# md_mini_smd.net
KiCad netlist of a schematic drawn in EAGLE
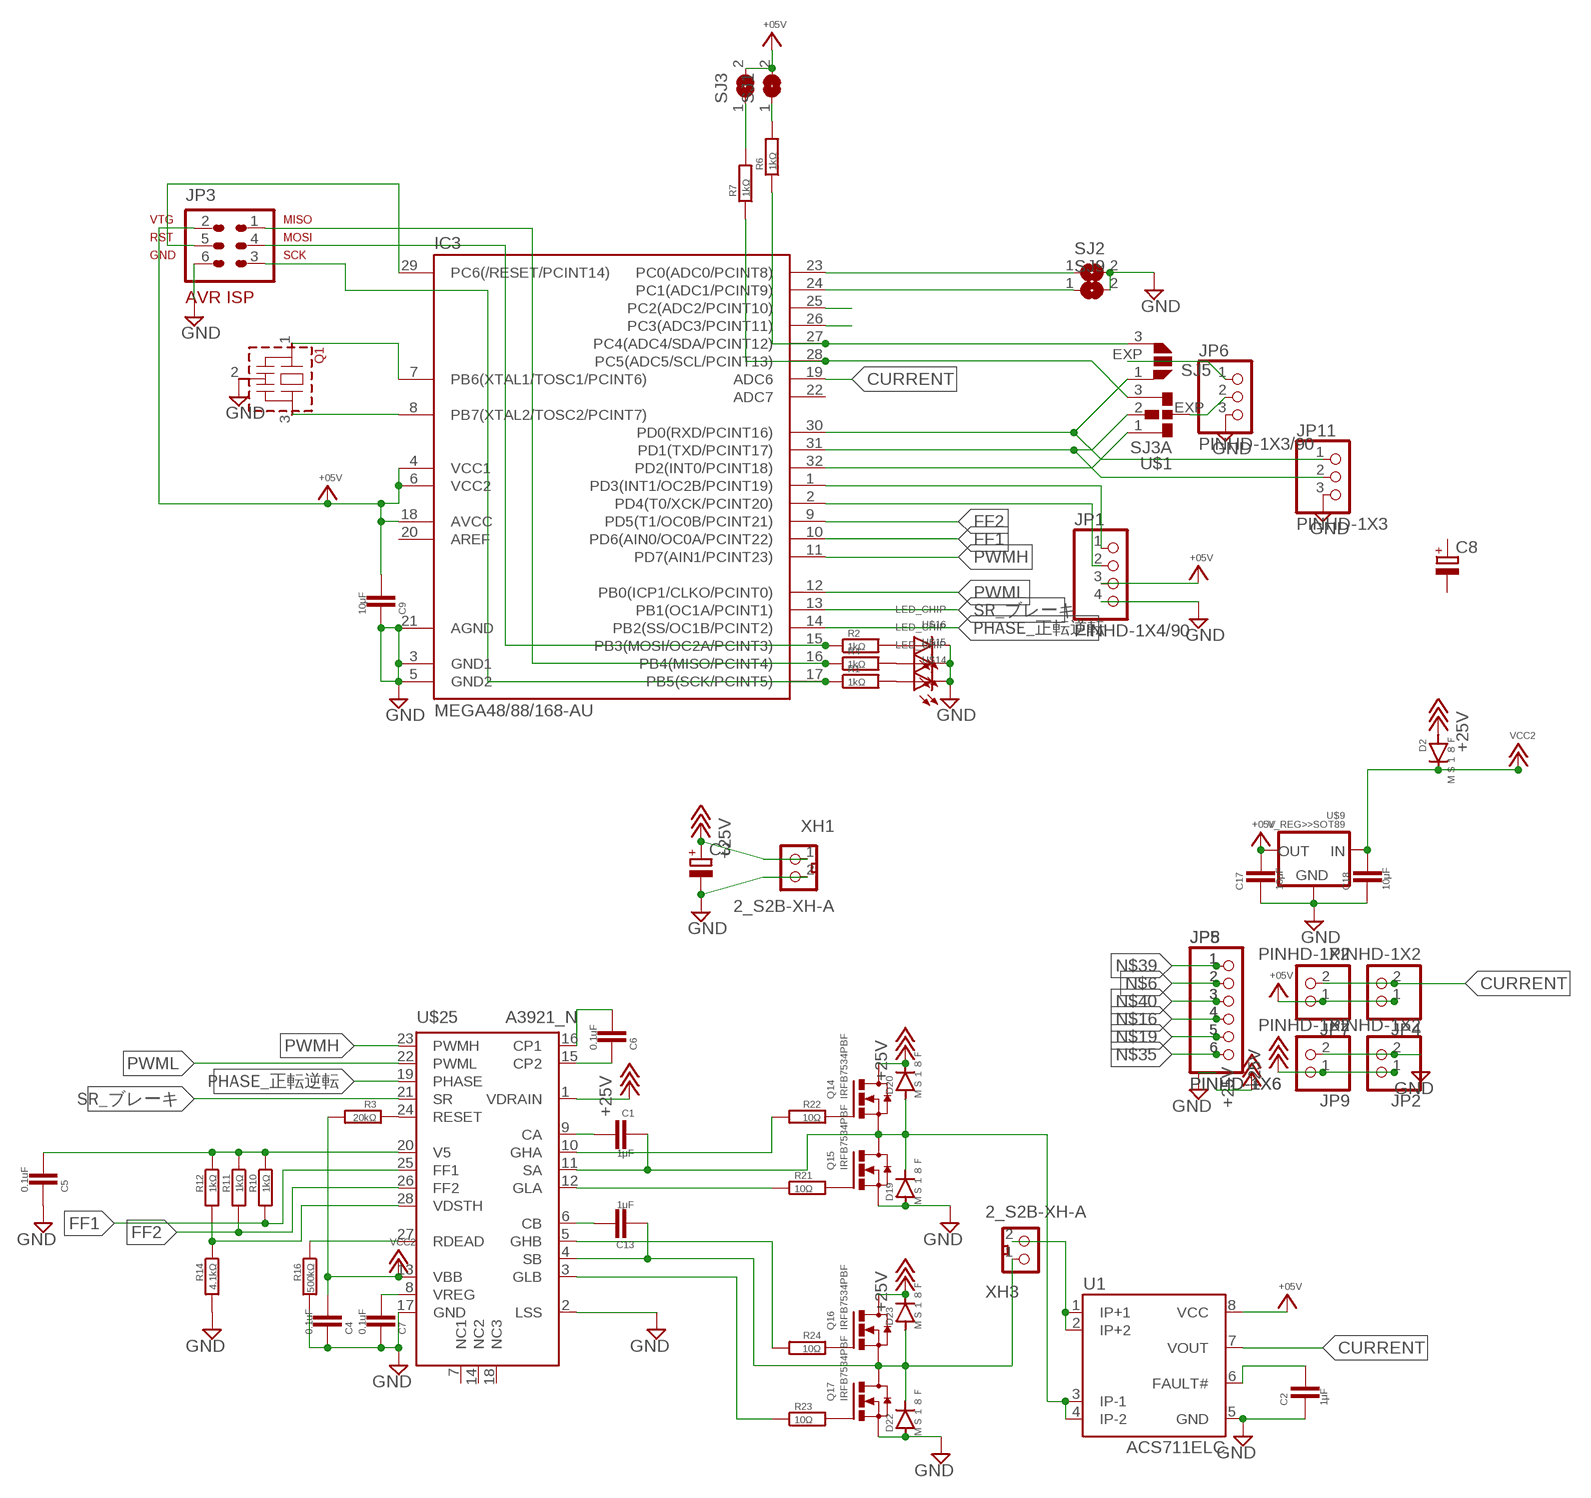
[diagram p0: schematic, sheet 1]

(export (version "E")
  (design (tool "Eeschema 10.0.6"))
  (components
    (comp (ref "C1")
      (value "1μF")
      (footprint "eagle-import:2012")
      (libsource (lib "eagle-import") (part "CAPACITOR{gt}{gt}2012"))
    )
    (comp (ref "C2")
      (value "1μF")
      (footprint "eagle-import:2012")
      (libsource (lib "eagle-import") (part "CAPACITOR{gt}{gt}2012"))
    )
    (comp (ref "C3")
      (value "CPOL-EUUD-6,3X8,8")
      (footprint "eagle-import:UD-6,3X5,8_NICHICON")
      (libsource (lib "eagle-import") (part "CPOL-EUUD-6,3X8,8"))
    )
    (comp (ref "C4")
      (value "0.1uF")
      (footprint "eagle-import:2012")
      (libsource (lib "eagle-import") (part "CAPACITOR{gt}{gt}2012"))
    )
    (comp (ref "C5")
      (value "0.1uF")
      (footprint "eagle-import:2012")
      (libsource (lib "eagle-import") (part "CAPACITOR{gt}{gt}2012"))
    )
    (comp (ref "C6")
      (value "0.1uF")
      (footprint "eagle-import:2012")
      (libsource (lib "eagle-import") (part "CAPACITOR{gt}{gt}2012"))
    )
    (comp (ref "C7")
      (value "0.1uF")
      (footprint "eagle-import:2012")
      (libsource (lib "eagle-import") (part "CAPACITOR{gt}{gt}2012"))
    )
    (comp (ref "C8")
      (value "CPOL-EU150CLZ-1010")
      (footprint "eagle-import:150CLZ-1010")
      (libsource (lib "eagle-import") (part "CPOL-EU150CLZ-1010"))
    )
    (comp (ref "C9")
      (value "10μF")
      (footprint "eagle-import:2012")
      (libsource (lib "eagle-import") (part "CAPACITOR{gt}{gt}2012"))
    )
    (comp (ref "C13")
      (value "1μF")
      (footprint "eagle-import:2012")
      (libsource (lib "eagle-import") (part "CAPACITOR{gt}{gt}2012"))
    )
    (comp (ref "C17")
      (value "10μF")
      (footprint "eagle-import:2012")
      (libsource (lib "eagle-import") (part "CAPACITOR{gt}{gt}2012"))
    )
    (comp (ref "C18")
      (value "10μF")
      (footprint "eagle-import:2012")
      (libsource (lib "eagle-import") (part "CAPACITOR{gt}{gt}2012"))
    )
    (comp (ref "D2")
      (value "ＭＳ１８Ｆ")
      (footprint "eagle-import:MS18F")
      (libsource (lib "eagle-import") (part "DIODE{gt}{gt}MS18F"))
    )
    (comp (ref "D19")
      (value "ＭＳ１８Ｆ")
      (footprint "eagle-import:MS18F")
      (libsource (lib "eagle-import") (part "DIODE{gt}{gt}MS18F"))
    )
    (comp (ref "D20")
      (value "ＭＳ１８Ｆ")
      (footprint "eagle-import:MS18F")
      (libsource (lib "eagle-import") (part "DIODE{gt}{gt}MS18F"))
    )
    (comp (ref "D22")
      (value "ＭＳ１８Ｆ")
      (footprint "eagle-import:MS18F")
      (libsource (lib "eagle-import") (part "DIODE{gt}{gt}MS18F"))
    )
    (comp (ref "D23")
      (value "ＭＳ１８Ｆ")
      (footprint "eagle-import:MS18F")
      (libsource (lib "eagle-import") (part "DIODE{gt}{gt}MS18F"))
    )
    (comp (ref "IC3")
      (value "MEGA48/88/168-AU")
      (footprint "eagle-import:TQFP32-08")
      (libsource (lib "eagle-import") (part "MEGA48/88/168-AU"))
    )
    (comp (ref "JP1")
      (value "PINHD-1X4/90")
      (footprint "eagle-import:1X04_90")
      (libsource (lib "eagle-import") (part "PINHD-1X4/90"))
    )
    (comp (ref "JP2")
      (value "PINHD-1X2")
      (footprint "eagle-import:1X02")
      (libsource (lib "eagle-import") (part "PINHD-1X2"))
    )
    (comp (ref "JP3")
      (value "AVR-ISP-6")
      (footprint "eagle-import:AVR-ISP-6")
      (libsource (lib "eagle-import") (part "AVR-ISP-6"))
    )
    (comp (ref "JP4")
      (value "PINHD-1X2")
      (footprint "eagle-import:1X02")
      (libsource (lib "eagle-import") (part "PINHD-1X2"))
    )
    (comp (ref "JP5")
      (value "PINHD-1X6")
      (footprint "eagle-import:1X06")
      (libsource (lib "eagle-import") (part "PINHD-1X6"))
    )
    (comp (ref "JP6")
      (value "PINHD-1X3/90")
      (footprint "eagle-import:1X03_90")
      (libsource (lib "eagle-import") (part "PINHD-1X3/90"))
    )
    (comp (ref "JP7")
      (value "PINHD-1X2")
      (footprint "eagle-import:1X02")
      (libsource (lib "eagle-import") (part "PINHD-1X2"))
    )
    (comp (ref "JP8")
      (value "PINHD-1X6")
      (footprint "eagle-import:1X06")
      (libsource (lib "eagle-import") (part "PINHD-1X6"))
    )
    (comp (ref "JP9")
      (value "PINHD-1X2")
      (footprint "eagle-import:1X02")
      (libsource (lib "eagle-import") (part "PINHD-1X2"))
    )
    (comp (ref "JP11")
      (value "PINHD-1X3")
      (footprint "eagle-import:1X03")
      (libsource (lib "eagle-import") (part "PINHD-1X3"))
    )
    (comp (ref "Q1")
      (value "CSTLS_G")
      (footprint "eagle-import:CSTLS_G9")
      (libsource (lib "eagle-import") (part "!murata-resonators(ｾﾗﾛｯｸ)_CSTLS_G"))
    )
    (comp (ref "Q14")
      (value "IRFB7534PBF")
      (footprint "eagle-import:TO252")
      (libsource (lib "eagle-import") (part "MOSFET_N{gt}{gt}TO252"))
    )
    (comp (ref "Q15")
      (value "IRFB7534PBF")
      (footprint "eagle-import:TO252")
      (libsource (lib "eagle-import") (part "MOSFET_N{gt}{gt}TO252"))
    )
    (comp (ref "Q16")
      (value "IRFB7534PBF")
      (footprint "eagle-import:TO252")
      (libsource (lib "eagle-import") (part "MOSFET_N{gt}{gt}TO252"))
    )
    (comp (ref "Q17")
      (value "IRFB7534PBF")
      (footprint "eagle-import:TO252")
      (libsource (lib "eagle-import") (part "MOSFET_N{gt}{gt}TO252"))
    )
    (comp (ref "R1")
      (value "1kΩ")
      (footprint "eagle-import:1608")
      (libsource (lib "eagle-import") (part "REGISTER{gt}{gt}1608"))
    )
    (comp (ref "R2")
      (value "1kΩ")
      (footprint "eagle-import:1608")
      (libsource (lib "eagle-import") (part "REGISTER{gt}{gt}1608"))
    )
    (comp (ref "R3")
      (value "20kΩ")
      (footprint "eagle-import:1608")
      (libsource (lib "eagle-import") (part "REGISTER{gt}{gt}1608"))
    )
    (comp (ref "R4")
      (value "1kΩ")
      (footprint "eagle-import:1608")
      (libsource (lib "eagle-import") (part "REGISTER{gt}{gt}1608"))
    )
    (comp (ref "R6")
      (value "1kΩ")
      (footprint "eagle-import:1608")
      (libsource (lib "eagle-import") (part "REGISTER{gt}{gt}1608"))
    )
    (comp (ref "R7")
      (value "1kΩ")
      (footprint "eagle-import:1608")
      (libsource (lib "eagle-import") (part "REGISTER{gt}{gt}1608"))
    )
    (comp (ref "R10")
      (value "1kΩ")
      (footprint "eagle-import:1608")
      (libsource (lib "eagle-import") (part "REGISTER{gt}{gt}1608"))
    )
    (comp (ref "R11")
      (value "1kΩ")
      (footprint "eagle-import:1608")
      (libsource (lib "eagle-import") (part "REGISTER{gt}{gt}1608"))
    )
    (comp (ref "R12")
      (value "1kΩ")
      (footprint "eagle-import:1608")
      (libsource (lib "eagle-import") (part "REGISTER{gt}{gt}1608"))
    )
    (comp (ref "R14")
      (value "4.1kΩ")
      (footprint "eagle-import:1608")
      (libsource (lib "eagle-import") (part "REGISTER{gt}{gt}1608"))
    )
    (comp (ref "R16")
      (value "500kΩ")
      (footprint "eagle-import:1608")
      (libsource (lib "eagle-import") (part "REGISTER{gt}{gt}1608"))
    )
    (comp (ref "R21")
      (value "10Ω")
      (footprint "eagle-import:1608")
      (libsource (lib "eagle-import") (part "REGISTER{gt}{gt}1608"))
    )
    (comp (ref "R22")
      (value "10Ω")
      (footprint "eagle-import:1608")
      (libsource (lib "eagle-import") (part "REGISTER{gt}{gt}1608"))
    )
    (comp (ref "R23")
      (value "10Ω")
      (footprint "eagle-import:1608")
      (libsource (lib "eagle-import") (part "REGISTER{gt}{gt}1608"))
    )
    (comp (ref "R24")
      (value "10Ω")
      (footprint "eagle-import:1608")
      (libsource (lib "eagle-import") (part "REGISTER{gt}{gt}1608"))
    )
    (comp (ref "SJ1")
      (value "SJSS")
      (footprint "eagle-import:SJ_B")
      (libsource (lib "eagle-import") (part "SJSS"))
    )
    (comp (ref "SJ2")
      (value "SJSS")
      (footprint "eagle-import:SJ_B")
      (libsource (lib "eagle-import") (part "SJSS"))
    )
    (comp (ref "SJ3")
      (value "SJSS")
      (footprint "eagle-import:SJ_B")
      (libsource (lib "eagle-import") (part "SJSS"))
    )
    (comp (ref "SJ5")
      (value "SJ2")
      (footprint "eagle-import:SJ2_A")
      (libsource (lib "eagle-import") (part "SJ2"))
    )
    (comp (ref "SJ9")
      (value "SJSS")
      (footprint "eagle-import:SJ_B")
      (libsource (lib "eagle-import") (part "SJSS"))
    )
    (comp (ref "U$1")
      (value "SJ3A")
      (footprint "eagle-import:SJ3_A")
      (libsource (lib "eagle-import") (part "SJ3A"))
    )
    (comp (ref "U$9")
      (value "V_REG>>SOT89")
      (footprint "eagle-import:SOT89")
      (libsource (lib "eagle-import") (part "V_REG{gt}{gt}SOT89"))
    )
    (comp (ref "U$14")
      (value "LED_CHIP")
      (footprint "eagle-import:2012")
      (libsource (lib "eagle-import") (part "LED_CHIP"))
    )
    (comp (ref "U$15")
      (value "LED_CHIP")
      (footprint "eagle-import:2012")
      (libsource (lib "eagle-import") (part "LED_CHIP"))
    )
    (comp (ref "U$16")
      (value "LED_CHIP")
      (footprint "eagle-import:2012")
      (libsource (lib "eagle-import") (part "LED_CHIP"))
    )
    (comp (ref "U$25")
      (value "A3921_N")
      (footprint "eagle-import:TSSOP28_N")
      (libsource (lib "eagle-import") (part "A3921_N"))
    )
    (comp (ref "U1")
      (value "ACS711ELC")
      (footprint "eagle-import:SOIC8")
      (libsource (lib "eagle-import") (part "ACS711ELC"))
    )
    (comp (ref "XH1")
      (value "2_S2B-XH-A")
      (footprint "eagle-import:S2B-XH-A")
      (libsource (lib "eagle-import") (part "2_S2B-XH-A"))
    )
    (comp (ref "XH3")
      (value "2_S2B-XH-A")
      (footprint "eagle-import:S2B-XH-A")
      (libsource (lib "eagle-import") (part "2_S2B-XH-A"))
    )
  )
  (nets
    (net (code "1") (name "+05V") (class "Default")
      (node (ref "C17") (pin "1") (pinfunction "1_1") (pintype "passive"))
      (node (ref "C9") (pin "1") (pinfunction "1_1") (pintype "passive"))
      (node (ref "IC3") (pin "18") (pinfunction "AVCC_18") (pintype "passive"))
      (node (ref "IC3") (pin "4") (pinfunction "VCC1_4") (pintype "power_in"))
      (node (ref "IC3") (pin "6") (pinfunction "VCC2_6") (pintype "power_in"))
      (node (ref "JP1") (pin "3") (pinfunction "3_3") (pintype "passive"))
      (node (ref "JP3") (pin "2") (pinfunction "2_2") (pintype "passive"))
      (node (ref "JP4") (pin "1") (pinfunction "1_1") (pintype "passive"))
      (node (ref "JP7") (pin "1") (pinfunction "1_1") (pintype "passive"))
      (node (ref "SJ1") (pin "2") (pinfunction "2_2") (pintype "passive"))
      (node (ref "SJ3") (pin "2") (pinfunction "2_2") (pintype "passive"))
      (node (ref "U$9") (pin "1") (pinfunction "OUT_1") (pintype "passive"))
      (node (ref "U1") (pin "8") (pinfunction "VCC_8") (pintype "bidirectional"))
    )
    (net (code "2") (name "+25V") (class "Default")
      (node (ref "C3") (pin "+") (pinfunction "+_+") (pintype "passive"))
      (node (ref "D2") (pin "P$1") (pinfunction "A_P$1") (pintype "passive"))
      (node (ref "D20") (pin "P$2") (pinfunction "C_P$2") (pintype "passive"))
      (node (ref "D23") (pin "P$2") (pinfunction "C_P$2") (pintype "passive"))
      (node (ref "JP2") (pin "1") (pinfunction "1_1") (pintype "passive"))
      (node (ref "JP9") (pin "1") (pinfunction "1_1") (pintype "passive"))
      (node (ref "Q14") (pin "3") (pinfunction "D_3") (pintype "passive"))
      (node (ref "Q16") (pin "3") (pinfunction "D_3") (pintype "passive"))
      (node (ref "U$25") (pin "1") (pinfunction "VDRAIN_1") (pintype "power_in"))
      (node (ref "XH1") (pin "1") (pinfunction "1_1") (pintype "passive"))
    )
    (net (code "3") (name "CURRENT") (class "Default")
      (node (ref "IC3") (pin "19") (pinfunction "ADC6_19") (pintype "passive"))
      (node (ref "JP4") (pin "2") (pinfunction "2_2") (pintype "passive"))
      (node (ref "JP7") (pin "2") (pinfunction "2_2") (pintype "passive"))
      (node (ref "U1") (pin "7") (pinfunction "VOUT_7") (pintype "bidirectional"))
    )
    (net (code "4") (name "FF1") (class "Default")
      (node (ref "IC3") (pin "10") (pinfunction "PD6(AIN0/OC0A/PCINT22)_10") (pintype "bidirectional"))
      (node (ref "R10") (pin "2") (pinfunction "2_2") (pintype "passive"))
      (node (ref "U$25") (pin "25") (pinfunction "FF1_25") (pintype "output"))
    )
    (net (code "5") (name "FF2") (class "Default")
      (node (ref "IC3") (pin "9") (pinfunction "PD5(T1/OC0B/PCINT21)_9") (pintype "bidirectional"))
      (node (ref "R11") (pin "2") (pinfunction "2_2") (pintype "passive"))
      (node (ref "U$25") (pin "26") (pinfunction "FF2_26") (pintype "output"))
    )
    (net (code "6") (name "GND") (class "Default")
      (node (ref "C17") (pin "2") (pinfunction "2_2") (pintype "passive"))
      (node (ref "C18") (pin "2") (pinfunction "2_2") (pintype "passive"))
      (node (ref "C2") (pin "2") (pinfunction "2_2") (pintype "passive"))
      (node (ref "C3") (pin "-") (pinfunction "-_-") (pintype "passive"))
      (node (ref "C4") (pin "2") (pinfunction "2_2") (pintype "passive"))
      (node (ref "C5") (pin "2") (pinfunction "2_2") (pintype "passive"))
      (node (ref "C7") (pin "2") (pinfunction "2_2") (pintype "passive"))
      (node (ref "C9") (pin "2") (pinfunction "2_2") (pintype "passive"))
      (node (ref "D19") (pin "P$1") (pinfunction "A_P$1") (pintype "passive"))
      (node (ref "D22") (pin "P$1") (pinfunction "A_P$1") (pintype "passive"))
      (node (ref "IC3") (pin "21") (pinfunction "AGND_21") (pintype "power_in"))
      (node (ref "IC3") (pin "3") (pinfunction "GND1_3") (pintype "power_in"))
      (node (ref "IC3") (pin "5") (pinfunction "GND2_5") (pintype "power_in"))
      (node (ref "JP1") (pin "4") (pinfunction "4_4") (pintype "passive"))
      (node (ref "JP11") (pin "3") (pinfunction "3_3") (pintype "passive"))
      (node (ref "JP2") (pin "2") (pinfunction "2_2") (pintype "passive"))
      (node (ref "JP3") (pin "6") (pinfunction "6_6") (pintype "passive"))
      (node (ref "JP6") (pin "3") (pinfunction "3_3") (pintype "passive"))
      (node (ref "JP9") (pin "2") (pinfunction "2_2") (pintype "passive"))
      (node (ref "Q1") (pin "2") (pinfunction "VSS_2") (pintype "power_in"))
      (node (ref "Q15") (pin "2") (pinfunction "S_2") (pintype "passive"))
      (node (ref "Q17") (pin "2") (pinfunction "S_2") (pintype "passive"))
      (node (ref "R14") (pin "2") (pinfunction "2_2") (pintype "passive"))
      (node (ref "R16") (pin "2") (pinfunction "2_2") (pintype "passive"))
      (node (ref "SJ2") (pin "2") (pinfunction "2_2") (pintype "passive"))
      (node (ref "SJ9") (pin "2") (pinfunction "2_2") (pintype "passive"))
      (node (ref "U$14") (pin "P$2") (pinfunction "C_P$2") (pintype "passive"))
      (node (ref "U$15") (pin "P$2") (pinfunction "C_P$2") (pintype "passive"))
      (node (ref "U$16") (pin "P$2") (pinfunction "C_P$2") (pintype "passive"))
      (node (ref "U$25") (pin "17") (pinfunction "GND_17") (pintype "power_in"))
      (node (ref "U$25") (pin "2") (pinfunction "LSS_2") (pintype "passive"))
      (node (ref "U$9") (pin "2") (pinfunction "GND_2") (pintype "input"))
      (node (ref "U$9") (pin "2.1") (pinfunction "GND_2.1") (pintype "input"))
      (node (ref "U1") (pin "5") (pinfunction "GND_5") (pintype "bidirectional"))
      (node (ref "XH1") (pin "2") (pinfunction "2_2") (pintype "passive"))
    )
    (net (code "7") (name "N$6") (class "Default")
      (node (ref "C13") (pin "2") (pinfunction "2_2") (pintype "passive"))
      (node (ref "D22") (pin "P$2") (pinfunction "C_P$2") (pintype "passive"))
      (node (ref "D23") (pin "P$1") (pinfunction "A_P$1") (pintype "passive"))
      (node (ref "JP5") (pin "2") (pinfunction "2_2") (pintype "passive"))
      (node (ref "JP8") (pin "2") (pinfunction "2_2") (pintype "passive"))
      (node (ref "Q16") (pin "2") (pinfunction "S_2") (pintype "passive"))
      (node (ref "Q17") (pin "3") (pinfunction "D_3") (pintype "passive"))
      (node (ref "U$25") (pin "4") (pinfunction "SB_4") (pintype "output"))
      (node (ref "XH3") (pin "1") (pinfunction "1_1") (pintype "passive"))
    )
    (net (code "8") (name "N$16") (class "Default")
      (node (ref "JP5") (pin "4") (pinfunction "4_4") (pintype "passive"))
      (node (ref "JP8") (pin "4") (pinfunction "4_4") (pintype "passive"))
      (node (ref "R22") (pin "2") (pinfunction "2_2") (pintype "passive"))
      (node (ref "U$25") (pin "10") (pinfunction "GHA_10") (pintype "output"))
    )
    (net (code "9") (name "N$19") (class "Default")
      (node (ref "C1") (pin "2") (pinfunction "2_2") (pintype "passive"))
      (node (ref "D19") (pin "P$2") (pinfunction "C_P$2") (pintype "passive"))
      (node (ref "D20") (pin "P$1") (pinfunction "A_P$1") (pintype "passive"))
      (node (ref "JP5") (pin "5") (pinfunction "5_5") (pintype "passive"))
      (node (ref "JP8") (pin "5") (pinfunction "5_5") (pintype "passive"))
      (node (ref "Q14") (pin "2") (pinfunction "S_2") (pintype "passive"))
      (node (ref "Q15") (pin "3") (pinfunction "D_3") (pintype "passive"))
      (node (ref "U$25") (pin "11") (pinfunction "SA_11") (pintype "output"))
      (node (ref "U1") (pin "3") (pinfunction "IP-1_3") (pintype "bidirectional"))
      (node (ref "U1") (pin "4") (pinfunction "IP-2_4") (pintype "bidirectional"))
    )
    (net (code "10") (name "N$35") (class "Default")
      (node (ref "JP5") (pin "6") (pinfunction "6_6") (pintype "passive"))
      (node (ref "JP8") (pin "6") (pinfunction "6_6") (pintype "passive"))
      (node (ref "R21") (pin "1") (pinfunction "1_1") (pintype "passive"))
      (node (ref "U$25") (pin "12") (pinfunction "GLA_12") (pintype "output"))
    )
    (net (code "11") (name "N$39") (class "Default")
      (node (ref "JP5") (pin "1") (pinfunction "1_1") (pintype "passive"))
      (node (ref "JP8") (pin "1") (pinfunction "1_1") (pintype "passive"))
      (node (ref "R24") (pin "2") (pinfunction "2_2") (pintype "passive"))
      (node (ref "U$25") (pin "5") (pinfunction "GHB_5") (pintype "output"))
    )
    (net (code "12") (name "N$40") (class "Default")
      (node (ref "JP5") (pin "3") (pinfunction "3_3") (pintype "passive"))
      (node (ref "JP8") (pin "3") (pinfunction "3_3") (pintype "passive"))
      (node (ref "R23") (pin "1") (pinfunction "1_1") (pintype "passive"))
      (node (ref "U$25") (pin "3") (pinfunction "GLB_3") (pintype "output"))
    )
    (net (code "13") (name "Net-(IC3-PB3(MOSI{slash}OC2A{slash}PCINT3))") (class "Default")
      (node (ref "IC3") (pin "15") (pinfunction "PB3(MOSI/OC2A/PCINT3)_15") (pintype "bidirectional"))
      (node (ref "JP3") (pin "4") (pinfunction "4_4") (pintype "passive"))
      (node (ref "R2") (pin "1") (pinfunction "1_1") (pintype "passive"))
    )
    (net (code "14") (name "Net-(IC3-PB4(MISO{slash}PCINT4))") (class "Default")
      (node (ref "IC3") (pin "16") (pinfunction "PB4(MISO/PCINT4)_16") (pintype "bidirectional"))
      (node (ref "JP3") (pin "1") (pinfunction "1_1") (pintype "passive"))
      (node (ref "R4") (pin "1") (pinfunction "1_1") (pintype "passive"))
    )
    (net (code "15") (name "Net-(IC3-PB5(SCK{slash}PCINT5))") (class "Default")
      (node (ref "IC3") (pin "17") (pinfunction "PB5(SCK/PCINT5)_17") (pintype "bidirectional"))
      (node (ref "JP3") (pin "3") (pinfunction "3_3") (pintype "passive"))
      (node (ref "R1") (pin "1") (pinfunction "1_1") (pintype "passive"))
    )
    (net (code "16") (name "Net-(IC3-PB6(XTAL1{slash}TOSC1{slash}PCINT6))") (class "Default")
      (node (ref "IC3") (pin "7") (pinfunction "PB6(XTAL1/TOSC1/PCINT6)_7") (pintype "bidirectional"))
      (node (ref "Q1") (pin "1") (pinfunction "1_1") (pintype "output"))
    )
    (net (code "17") (name "Net-(IC3-PB7(XTAL2{slash}TOSC2{slash}PCINT7))") (class "Default")
      (node (ref "IC3") (pin "8") (pinfunction "PB7(XTAL2/TOSC2/PCINT7)_8") (pintype "bidirectional"))
      (node (ref "Q1") (pin "3") (pinfunction "3_3") (pintype "input"))
    )
    (net (code "18") (name "Net-(IC3-PC0(ADC0{slash}PCINT8))") (class "Default")
      (node (ref "IC3") (pin "23") (pinfunction "PC0(ADC0/PCINT8)_23") (pintype "bidirectional"))
      (node (ref "SJ2") (pin "1") (pinfunction "1_1") (pintype "passive"))
    )
    (net (code "19") (name "Net-(IC3-PC1(ADC1{slash}PCINT9))") (class "Default")
      (node (ref "IC3") (pin "24") (pinfunction "PC1(ADC1/PCINT9)_24") (pintype "bidirectional"))
      (node (ref "SJ9") (pin "1") (pinfunction "1_1") (pintype "passive"))
    )
    (net (code "20") (name "Net-(IC3-PC4(ADC4{slash}SDA{slash}PCINT12))") (class "Default")
      (node (ref "IC3") (pin "27") (pinfunction "PC4(ADC4/SDA/PCINT12)_27") (pintype "bidirectional"))
      (node (ref "R6") (pin "1") (pinfunction "1_1") (pintype "passive"))
      (node (ref "SJ5") (pin "3") (pinfunction "3_3") (pintype "passive"))
    )
    (net (code "21") (name "Net-(IC3-PC5(ADC5{slash}SCL{slash}PCINT13))") (class "Default")
      (node (ref "IC3") (pin "28") (pinfunction "PC5(ADC5/SCL/PCINT13)_28") (pintype "bidirectional"))
      (node (ref "R7") (pin "1") (pinfunction "1_1") (pintype "passive"))
      (node (ref "U$1") (pin "3") (pinfunction "3_3") (pintype "passive"))
    )
    (net (code "22") (name "Net-(IC3-PC6({slash}RESET{slash}PCINT14))") (class "Default")
      (node (ref "IC3") (pin "29") (pinfunction "PC6(/RESET/PCINT14)_29") (pintype "bidirectional"))
      (node (ref "JP3") (pin "5") (pinfunction "5_5") (pintype "passive"))
    )
    (net (code "23") (name "Net-(IC3-PD0(RXD{slash}PCINT16))") (class "Default")
      (node (ref "IC3") (pin "30") (pinfunction "PD0(RXD/PCINT16)_30") (pintype "bidirectional"))
      (node (ref "JP11") (pin "1") (pinfunction "1_1") (pintype "passive"))
      (node (ref "SJ5") (pin "1") (pinfunction "1_1") (pintype "passive"))
    )
    (net (code "24") (name "Net-(IC3-PD1(TXD{slash}PCINT17))") (class "Default")
      (node (ref "IC3") (pin "31") (pinfunction "PD1(TXD/PCINT17)_31") (pintype "bidirectional"))
      (node (ref "JP11") (pin "2") (pinfunction "2_2") (pintype "passive"))
      (node (ref "U$1") (pin "2") (pinfunction "2_2") (pintype "passive"))
    )
    (net (code "25") (name "Net-(IC3-PD2(INT0{slash}PCINT18))") (class "Default")
      (node (ref "IC3") (pin "32") (pinfunction "PD2(INT0/PCINT18)_32") (pintype "bidirectional"))
      (node (ref "U$1") (pin "1") (pinfunction "1_1") (pintype "passive"))
    )
    (net (code "26") (name "Net-(IC3-PD3(INT1{slash}OC2B{slash}PCINT19))") (class "Default")
      (node (ref "IC3") (pin "1") (pinfunction "PD3(INT1/OC2B/PCINT19)_1") (pintype "bidirectional"))
      (node (ref "JP1") (pin "1") (pinfunction "1_1") (pintype "passive"))
    )
    (net (code "27") (name "Net-(IC3-PD4(T0{slash}XCK{slash}PCINT20))") (class "Default")
      (node (ref "IC3") (pin "2") (pinfunction "PD4(T0/XCK/PCINT20)_2") (pintype "bidirectional"))
      (node (ref "JP1") (pin "2") (pinfunction "2_2") (pintype "passive"))
    )
    (net (code "28") (name "Net-(JP6-Pad2)") (class "Default")
      (node (ref "JP6") (pin "2") (pinfunction "2_2") (pintype "passive"))
      (node (ref "U$1") (pin "EXP") (pinfunction "EXP_EXP") (pintype "passive"))
    )
    (net (code "29") (name "Net-(Q14-G)") (class "Default")
      (node (ref "Q14") (pin "1") (pinfunction "G_1") (pintype "passive"))
      (node (ref "R22") (pin "1") (pinfunction "1_1") (pintype "passive"))
    )
    (net (code "30") (name "Net-(Q15-G)") (class "Default")
      (node (ref "Q15") (pin "1") (pinfunction "G_1") (pintype "passive"))
      (node (ref "R21") (pin "2") (pinfunction "2_2") (pintype "passive"))
    )
    (net (code "31") (name "Net-(Q16-G)") (class "Default")
      (node (ref "Q16") (pin "1") (pinfunction "G_1") (pintype "passive"))
      (node (ref "R24") (pin "1") (pinfunction "1_1") (pintype "passive"))
    )
    (net (code "32") (name "Net-(Q17-G)") (class "Default")
      (node (ref "Q17") (pin "1") (pinfunction "G_1") (pintype "passive"))
      (node (ref "R23") (pin "2") (pinfunction "2_2") (pintype "passive"))
    )
    (net (code "33") (name "Net-(R6-Pad2)") (class "Default")
      (node (ref "R6") (pin "2") (pinfunction "2_2") (pintype "passive"))
      (node (ref "SJ1") (pin "1") (pinfunction "1_1") (pintype "passive"))
    )
    (net (code "34") (name "Net-(R7-Pad2)") (class "Default")
      (node (ref "R7") (pin "2") (pinfunction "2_2") (pintype "passive"))
      (node (ref "SJ3") (pin "1") (pinfunction "1_1") (pintype "passive"))
    )
    (net (code "35") (name "Net-(SJ5-2)") (class "Default")
      (node (ref "JP6") (pin "1") (pinfunction "1_1") (pintype "passive"))
      (node (ref "SJ5") (pin "EXP") (pinfunction "2_EXP") (pintype "passive"))
    )
    (net (code "36") (name "Net-(U$14-A)") (class "Default")
      (node (ref "R1") (pin "2") (pinfunction "2_2") (pintype "passive"))
      (node (ref "U$14") (pin "P$1") (pinfunction "A_P$1") (pintype "passive"))
    )
    (net (code "37") (name "Net-(U$15-A)") (class "Default")
      (node (ref "R4") (pin "2") (pinfunction "2_2") (pintype "passive"))
      (node (ref "U$15") (pin "P$1") (pinfunction "A_P$1") (pintype "passive"))
    )
    (net (code "38") (name "Net-(U$16-A)") (class "Default")
      (node (ref "R2") (pin "2") (pinfunction "2_2") (pintype "passive"))
      (node (ref "U$16") (pin "P$1") (pinfunction "A_P$1") (pintype "passive"))
    )
    (net (code "39") (name "Net-(U$25-CA)") (class "Default")
      (node (ref "C1") (pin "1") (pinfunction "1_1") (pintype "passive"))
      (node (ref "U$25") (pin "9") (pinfunction "CA_9") (pintype "input"))
    )
    (net (code "40") (name "Net-(U$25-CB)") (class "Default")
      (node (ref "C13") (pin "1") (pinfunction "1_1") (pintype "passive"))
      (node (ref "U$25") (pin "6") (pinfunction "CB_6") (pintype "input"))
    )
    (net (code "41") (name "Net-(U$25-CP1)") (class "Default")
      (node (ref "C6") (pin "1") (pinfunction "1_1") (pintype "passive"))
      (node (ref "U$25") (pin "16") (pinfunction "CP1_16") (pintype "passive"))
    )
    (net (code "42") (name "Net-(U$25-CP2)") (class "Default")
      (node (ref "C6") (pin "2") (pinfunction "2_2") (pintype "passive"))
      (node (ref "U$25") (pin "15") (pinfunction "CP2_15") (pintype "passive"))
    )
    (net (code "43") (name "Net-(U$25-RDEAD)") (class "Default")
      (node (ref "R16") (pin "1") (pinfunction "1_1") (pintype "passive"))
      (node (ref "U$25") (pin "27") (pinfunction "RDEAD_27") (pintype "input"))
    )
    (net (code "44") (name "Net-(U$25-RESET)") (class "Default")
      (node (ref "R3") (pin "1") (pinfunction "1_1") (pintype "passive"))
      (node (ref "U$25") (pin "24") (pinfunction "RESET_24") (pintype "input"))
    )
    (net (code "45") (name "Net-(U$25-V5)") (class "Default")
      (node (ref "C5") (pin "1") (pinfunction "1_1") (pintype "passive"))
      (node (ref "R10") (pin "1") (pinfunction "1_1") (pintype "passive"))
      (node (ref "R11") (pin "1") (pinfunction "1_1") (pintype "passive"))
      (node (ref "R12") (pin "1") (pinfunction "1_1") (pintype "passive"))
      (node (ref "U$25") (pin "20") (pinfunction "V5_20") (pintype "power_in"))
    )
    (net (code "46") (name "Net-(U$25-VDSTH)") (class "Default")
      (node (ref "R12") (pin "2") (pinfunction "2_2") (pintype "passive"))
      (node (ref "R14") (pin "1") (pinfunction "1_1") (pintype "passive"))
      (node (ref "U$25") (pin "28") (pinfunction "VDSTH_28") (pintype "input"))
    )
    (net (code "47") (name "Net-(U$25-VREG)") (class "Default")
      (node (ref "C7") (pin "1") (pinfunction "1_1") (pintype "passive"))
      (node (ref "U$25") (pin "8") (pinfunction "VREG_8") (pintype "power_in"))
    )
    (net (code "48") (name "Net-(U1-FAULT#)") (class "Default")
      (node (ref "C2") (pin "1") (pinfunction "1_1") (pintype "passive"))
      (node (ref "U1") (pin "6") (pinfunction "FAULT#_6") (pintype "bidirectional"))
    )
    (net (code "49") (name "Net-(U1-IP+1)") (class "Default")
      (node (ref "U1") (pin "1") (pinfunction "IP+1_1") (pintype "bidirectional"))
      (node (ref "U1") (pin "2") (pinfunction "IP+2_2") (pintype "bidirectional"))
      (node (ref "XH3") (pin "2") (pinfunction "2_2") (pintype "passive"))
    )
    (net (code "50") (name "PHASE_正転逆転") (class "Default")
      (node (ref "IC3") (pin "14") (pinfunction "PB2(SS/OC1B/PCINT2)_14") (pintype "bidirectional"))
      (node (ref "U$25") (pin "19") (pinfunction "PHASE_19") (pintype "input"))
    )
    (net (code "51") (name "PWMH") (class "Default")
      (node (ref "IC3") (pin "11") (pinfunction "PD7(AIN1/PCINT23)_11") (pintype "bidirectional"))
      (node (ref "U$25") (pin "23") (pinfunction "PWMH_23") (pintype "input"))
    )
    (net (code "52") (name "PWML") (class "Default")
      (node (ref "IC3") (pin "12") (pinfunction "PB0(ICP1/CLKO/PCINT0)_12") (pintype "bidirectional"))
      (node (ref "U$25") (pin "22") (pinfunction "PWML_22") (pintype "input"))
    )
    (net (code "53") (name "SR_ブレーキ") (class "Default")
      (node (ref "IC3") (pin "13") (pinfunction "PB1(OC1A/PCINT1)_13") (pintype "bidirectional"))
      (node (ref "U$25") (pin "21") (pinfunction "SR_21") (pintype "input"))
    )
    (net (code "54") (name "VCC2") (class "Default")
      (node (ref "C18") (pin "1") (pinfunction "1_1") (pintype "passive"))
      (node (ref "C4") (pin "1") (pinfunction "1_1") (pintype "passive"))
      (node (ref "D2") (pin "P$2") (pinfunction "C_P$2") (pintype "passive"))
      (node (ref "R3") (pin "2") (pinfunction "2_2") (pintype "passive"))
      (node (ref "U$25") (pin "13") (pinfunction "VBB_13") (pintype "power_in"))
      (node (ref "U$9") (pin "3") (pinfunction "IN_3") (pintype "input"))
    )
    (net (code "55") (name "unconnected-(C8-Pad+)") (class "Default")
      (node (ref "C8") (pin "+") (pinfunction "+_+") (pintype "passive"))
    )
    (net (code "56") (name "unconnected-(C8-Pad-)") (class "Default")
      (node (ref "C8") (pin "-") (pinfunction "-_-") (pintype "passive"))
    )
    (net (code "57") (name "unconnected-(IC3-ADC7-Pad22)") (class "Default")
      (node (ref "IC3") (pin "22") (pinfunction "ADC7_22") (pintype "passive"))
    )
    (net (code "58") (name "unconnected-(IC3-AREF-Pad20)") (class "Default")
      (node (ref "IC3") (pin "20") (pinfunction "AREF_20") (pintype "passive"))
    )
    (net (code "59") (name "unconnected-(IC3-PC2(ADC2{slash}PCINT10)-Pad25)") (class "Default")
      (node (ref "IC3") (pin "25") (pinfunction "PC2(ADC2/PCINT10)_25") (pintype "bidirectional"))
    )
    (net (code "60") (name "unconnected-(IC3-PC3(ADC3{slash}PCINT11)-Pad26)") (class "Default")
      (node (ref "IC3") (pin "26") (pinfunction "PC3(ADC3/PCINT11)_26") (pintype "bidirectional"))
    )
    (net (code "61") (name "unconnected-(U$25-NC1-Pad7)") (class "Default")
      (node (ref "U$25") (pin "7") (pinfunction "NC1_7") (pintype "no_connect"))
    )
    (net (code "62") (name "unconnected-(U$25-NC2-Pad14)") (class "Default")
      (node (ref "U$25") (pin "14") (pinfunction "NC2_14") (pintype "no_connect"))
    )
    (net (code "63") (name "unconnected-(U$25-NC3-Pad18)") (class "Default")
      (node (ref "U$25") (pin "18") (pinfunction "NC3_18") (pintype "no_connect"))
    )
  )
)
